# UWB.net
KiCad netlist of a schematic drawn in Altium Designer
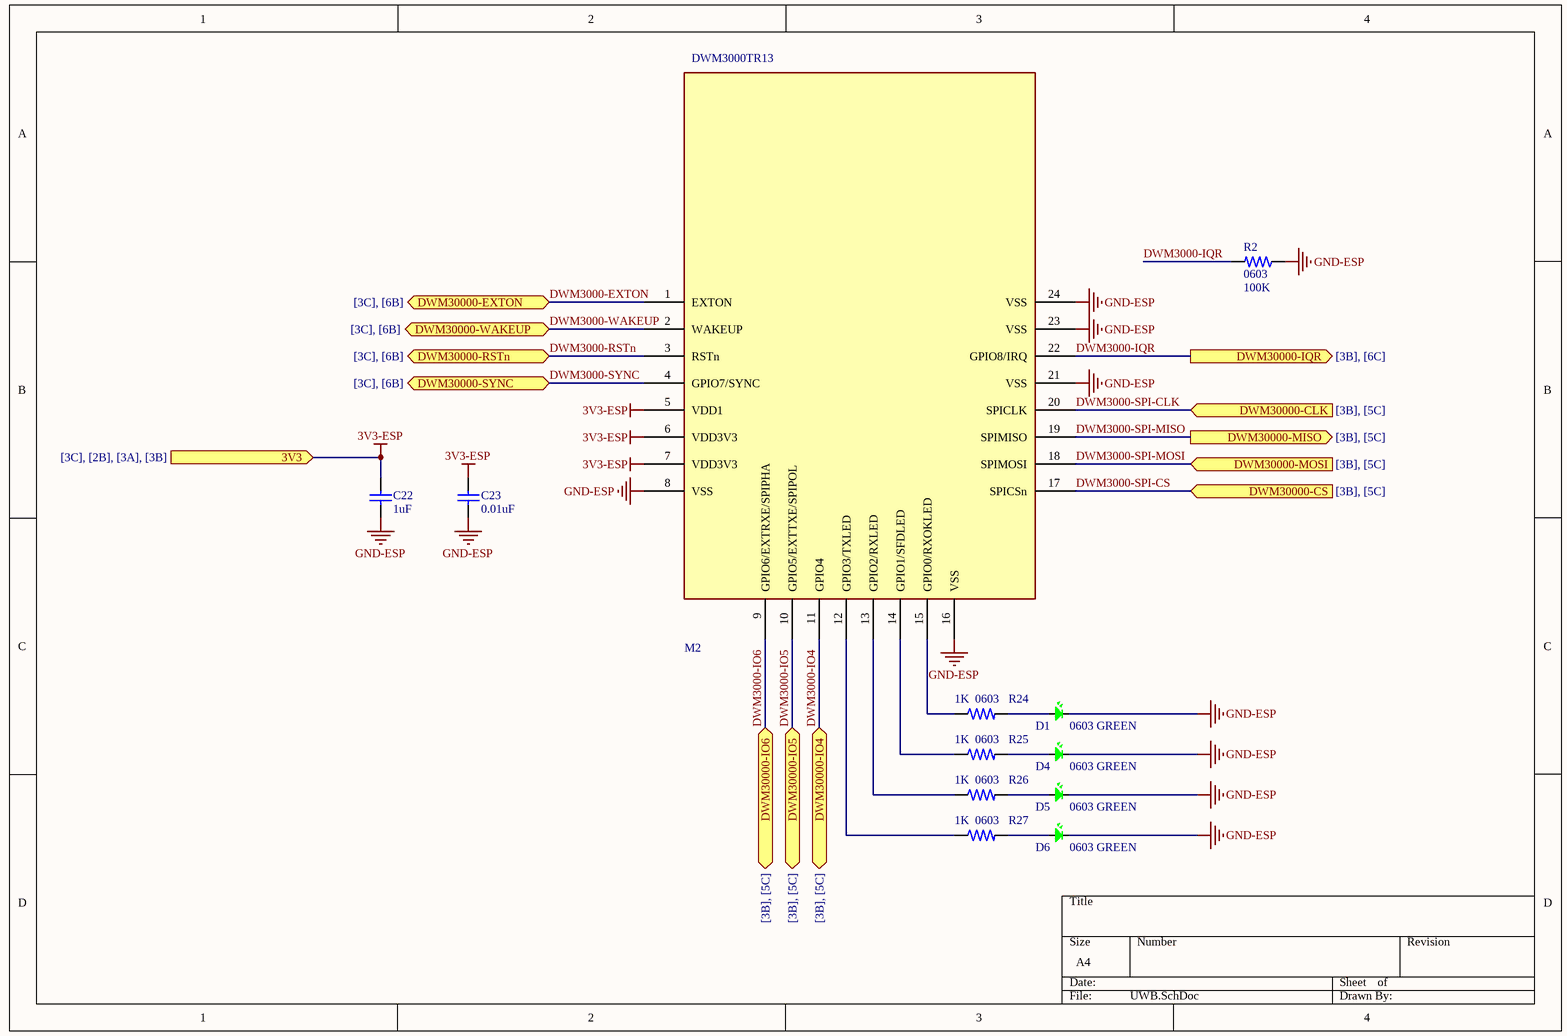
[diagram p0: UWB.SchDoc]

(export (version "E")
  (design (tool "Eeschema 10.0.6"))
  (components
    (comp (ref "C22")
      (value "1uF")
      (footprint "SMD-CAP-0603-YAGEO")
      (description "0603 1 uF 16 V ±10 % Tolerance X7R SMT Multilayer Ceramic Capacitor")
      (fields
        (field (name "MANUFACTURER") "Yageo")
        (field (name "MANUFACTURER PART NUMBER") "CC0603KRX7R7BB105")
        (field (name "DESIGNER") "TVBac")
      )
      (libsource (lib "Capacitors") (part "CAP; 1uF; 16V; 0603; SMD; CC0603KRX7R7BB105"))
    )
    (comp (ref "C23")
      (value "0.01uF")
      (footprint "SMD-CAP-0603-YAGEO")
      (description "Multilayer Ceramic Capacitor, 0.1 uF, 10 V, ± 10%, X7R, 0603 [1608 Metric]")
      (fields
        (field (name "MANUFACTURER") "Yageo")
        (field (name "MANUFACTURER PART NUMBER") "CC0603KRX7R6BB104")
        (field (name "DESIGNER") "TVBac")
      )
      (libsource (lib "Capacitors") (part "CAP; 0.1uF; 10V; 0603; SMD; CC0603KRX7R6BB104"))
    )
    (comp (ref "D1")
      (value "0603 GREEN")
      (footprint "LED0603_GREEN")
      (fields
        (field (name "MANUFACTURER") "Amicc")
        (field (name "MANUFACTURE PART NUMBER") "A-SP192DGHC-C01-4T")
      )
      (libsource (lib "LED") (part "L0603_GREEN"))
    )
    (comp (ref "D4")
      (value "0603 GREEN")
      (footprint "LED0603_GREEN")
      (fields
        (field (name "MANUFACTURER") "Amicc")
        (field (name "MANUFACTURE PART NUMBER") "A-SP192DGHC-C01-4T")
      )
      (libsource (lib "LED") (part "L0603_GREEN"))
    )
    (comp (ref "D5")
      (value "0603 GREEN")
      (footprint "LED0603_GREEN")
      (fields
        (field (name "MANUFACTURER") "Amicc")
        (field (name "MANUFACTURE PART NUMBER") "A-SP192DGHC-C01-4T")
      )
      (libsource (lib "LED") (part "L0603_GREEN"))
    )
    (comp (ref "D6")
      (value "0603 GREEN")
      (footprint "LED0603_GREEN")
      (fields
        (field (name "MANUFACTURER") "Amicc")
        (field (name "MANUFACTURE PART NUMBER") "A-SP192DGHC-C01-4T")
      )
      (libsource (lib "LED") (part "L0603_GREEN"))
    )
    (comp (ref "M2")
      (value "802.15.4, Bluetooth, Cellular UWB, Zigbee® Transceiver Module 6.25GHz ~ 8.25GHz Integrated, Ceramic Patch Surface Mount")
      (footprint "MODULE-DWM3000SR")
      (description "RF Modules UWB XCVR Module")
      (fields (field (name "MANUFACTURER") "Qorvo") (field (name "MANUFACTURER PART NUMBER") "DWM3000TR13"))
      (libsource (lib "Modules") (part "DWM3000TR13"))
    )
    (comp (ref "R2")
      (value "100K")
      (footprint "SMD-RES-0603-SEI")
      (description "Res Thick Film 0603 100K Ohm 5% 0.25W(1/4W) ±200ppm/C Pad SMD Automotive T/R")
      (fields
        (field (name "MANUFACTURER") "Rohm")
        (field (name "MANUFACTURER PART NUMBER") "ESR03EZPJ104")
        (field (name "PACKAGE") "0603")
        (field (name "DESIGNER") "TVBac")
      )
      (libsource (lib "Resistors") (part "RES; 100K; 0603; SMD; ESR03EZPJ104"))
    )
    (comp (ref "R24")
      (value "1K")
      (footprint "SMD-RES-0603-SEI")
      (description "SMD Chip Resistor, 1 kOhm, ± 1%, 250 mW, 0603 [1608 Metric], Thick Film, Anti-Surge")
      (fields
        (field (name "MANUFACTURER") "Rohm")
        (field (name "MANUFACTURER PART NUMBER") "ESR03EZPF1001")
        (field (name "PACKAGE") "0603")
        (field (name "DESIGNER") "TVBac")
      )
      (libsource (lib "Resistors") (part "RES; 1K; 0603; SMD; ESR03EZPF1001"))
    )
    (comp (ref "R25")
      (value "1K")
      (footprint "SMD-RES-0603-SEI")
      (description "SMD Chip Resistor, 1 kOhm, ± 1%, 250 mW, 0603 [1608 Metric], Thick Film, Anti-Surge")
      (fields
        (field (name "MANUFACTURER") "Rohm")
        (field (name "MANUFACTURER PART NUMBER") "ESR03EZPF1001")
        (field (name "PACKAGE") "0603")
        (field (name "DESIGNER") "TVBac")
      )
      (libsource (lib "Resistors") (part "RES; 1K; 0603; SMD; ESR03EZPF1001"))
    )
    (comp (ref "R26")
      (value "1K")
      (footprint "SMD-RES-0603-SEI")
      (description "SMD Chip Resistor, 1 kOhm, ± 1%, 250 mW, 0603 [1608 Metric], Thick Film, Anti-Surge")
      (fields
        (field (name "MANUFACTURER") "Rohm")
        (field (name "MANUFACTURER PART NUMBER") "ESR03EZPF1001")
        (field (name "PACKAGE") "0603")
        (field (name "DESIGNER") "TVBac")
      )
      (libsource (lib "Resistors") (part "RES; 1K; 0603; SMD; ESR03EZPF1001"))
    )
    (comp (ref "R27")
      (value "1K")
      (footprint "SMD-RES-0603-SEI")
      (description "SMD Chip Resistor, 1 kOhm, ± 1%, 250 mW, 0603 [1608 Metric], Thick Film, Anti-Surge")
      (fields
        (field (name "MANUFACTURER") "Rohm")
        (field (name "MANUFACTURER PART NUMBER") "ESR03EZPF1001")
        (field (name "PACKAGE") "0603")
        (field (name "DESIGNER") "TVBac")
      )
      (libsource (lib "Resistors") (part "RES; 1K; 0603; SMD; ESR03EZPF1001"))
    )
  )
  (nets
    (net (code "1") (name "/DWM3000-EXTON") (class "Default")
      (node (ref "M2") (pin "1") (pinfunction "EXTON_1") (pintype "passive"))
    )
    (net (code "2") (name "/DWM3000-IO4") (class "Default")
      (node (ref "M2") (pin "11") (pinfunction "GPIO4_11") (pintype "passive"))
    )
    (net (code "3") (name "/DWM3000-IO5") (class "Default")
      (node (ref "M2") (pin "10") (pinfunction "GPIO5/EXTTXE/SPIPOL_10") (pintype "passive"))
    )
    (net (code "4") (name "/DWM3000-IO6") (class "Default")
      (node (ref "M2") (pin "9") (pinfunction "GPIO6/EXTRXE/SPIPHA_9") (pintype "passive"))
    )
    (net (code "5") (name "/DWM3000-IQR") (class "Default")
      (node (ref "M2") (pin "22") (pinfunction "GPIO8/IRQ_22") (pintype "passive"))
      (node (ref "R2") (pin "2") (pinfunction "2_2") (pintype "passive"))
    )
    (net (code "6") (name "/DWM3000-RSTn") (class "Default")
      (node (ref "M2") (pin "3") (pinfunction "RSTn_3") (pintype "passive"))
    )
    (net (code "7") (name "/DWM3000-SPI-CLK") (class "Default")
      (node (ref "M2") (pin "20") (pinfunction "SPICLK_20") (pintype "passive"))
    )
    (net (code "8") (name "/DWM3000-SPI-CS") (class "Default")
      (node (ref "M2") (pin "17") (pinfunction "SPICSn_17") (pintype "passive"))
    )
    (net (code "9") (name "/DWM3000-SPI-MISO") (class "Default")
      (node (ref "M2") (pin "19") (pinfunction "SPIMISO_19") (pintype "passive"))
    )
    (net (code "10") (name "/DWM3000-SPI-MOSI") (class "Default")
      (node (ref "M2") (pin "18") (pinfunction "SPIMOSI_18") (pintype "passive"))
    )
    (net (code "11") (name "/DWM3000-SYNC") (class "Default")
      (node (ref "M2") (pin "4") (pinfunction "GPIO7/SYNC_4") (pintype "passive"))
    )
    (net (code "12") (name "/DWM3000-WAKEUP") (class "Default")
      (node (ref "M2") (pin "2") (pinfunction "WAKEUP_2") (pintype "passive"))
    )
    (net (code "13") (name "3V3-ESP") (class "Default")
      (node (ref "C22") (pin "2") (pinfunction "2_2") (pintype "passive"))
      (node (ref "C23") (pin "2") (pinfunction "2_2") (pintype "passive"))
      (node (ref "M2") (pin "5") (pinfunction "VDD1_5") (pintype "passive"))
      (node (ref "M2") (pin "6") (pinfunction "VDD3V3_6") (pintype "passive"))
      (node (ref "M2") (pin "7") (pinfunction "VDD3V3_7") (pintype "passive"))
    )
    (net (code "14") (name "GND-ESP") (class "Default")
      (node (ref "C22") (pin "1") (pinfunction "1_1") (pintype "passive"))
      (node (ref "C23") (pin "1") (pinfunction "1_1") (pintype "passive"))
      (node (ref "D1") (pin "2") (pinfunction "2_2") (pintype "passive"))
      (node (ref "D4") (pin "2") (pinfunction "2_2") (pintype "passive"))
      (node (ref "D5") (pin "2") (pinfunction "2_2") (pintype "passive"))
      (node (ref "D6") (pin "2") (pinfunction "2_2") (pintype "passive"))
      (node (ref "M2") (pin "16") (pinfunction "VSS_16") (pintype "passive"))
      (node (ref "M2") (pin "21") (pinfunction "VSS_21") (pintype "passive"))
      (node (ref "M2") (pin "23") (pinfunction "VSS_23") (pintype "passive"))
      (node (ref "M2") (pin "24") (pinfunction "VSS_24") (pintype "passive"))
      (node (ref "M2") (pin "8") (pinfunction "VSS_8") (pintype "passive"))
      (node (ref "R2") (pin "1") (pinfunction "1_1") (pintype "passive"))
    )
    (net (code "15") (name "Net-(D1-Pad1)") (class "Default")
      (node (ref "D1") (pin "1") (pinfunction "1_1") (pintype "passive"))
      (node (ref "R24") (pin "2") (pinfunction "2_2") (pintype "passive"))
    )
    (net (code "16") (name "Net-(D4-Pad1)") (class "Default")
      (node (ref "D4") (pin "1") (pinfunction "1_1") (pintype "passive"))
      (node (ref "R25") (pin "2") (pinfunction "2_2") (pintype "passive"))
    )
    (net (code "17") (name "Net-(D5-Pad1)") (class "Default")
      (node (ref "D5") (pin "1") (pinfunction "1_1") (pintype "passive"))
      (node (ref "R26") (pin "2") (pinfunction "2_2") (pintype "passive"))
    )
    (net (code "18") (name "Net-(D6-Pad1)") (class "Default")
      (node (ref "D6") (pin "1") (pinfunction "1_1") (pintype "passive"))
      (node (ref "R27") (pin "2") (pinfunction "2_2") (pintype "passive"))
    )
    (net (code "19") (name "Net-(M2-GPIO0{slash}RXOKLED)") (class "Default")
      (node (ref "M2") (pin "15") (pinfunction "GPIO0/RXOKLED_15") (pintype "passive"))
      (node (ref "R24") (pin "1") (pinfunction "1_1") (pintype "passive"))
    )
    (net (code "20") (name "Net-(M2-GPIO1{slash}SFDLED)") (class "Default")
      (node (ref "M2") (pin "14") (pinfunction "GPIO1/SFDLED_14") (pintype "passive"))
      (node (ref "R25") (pin "1") (pinfunction "1_1") (pintype "passive"))
    )
    (net (code "21") (name "Net-(M2-GPIO2{slash}RXLED)") (class "Default")
      (node (ref "M2") (pin "13") (pinfunction "GPIO2/RXLED_13") (pintype "passive"))
      (node (ref "R26") (pin "1") (pinfunction "1_1") (pintype "passive"))
    )
    (net (code "22") (name "Net-(M2-GPIO3{slash}TXLED)") (class "Default")
      (node (ref "M2") (pin "12") (pinfunction "GPIO3/TXLED_12") (pintype "passive"))
      (node (ref "R27") (pin "1") (pinfunction "1_1") (pintype "passive"))
    )
  )
)
